# Main.net
KiCad netlist of a schematic drawn in Altium Designer
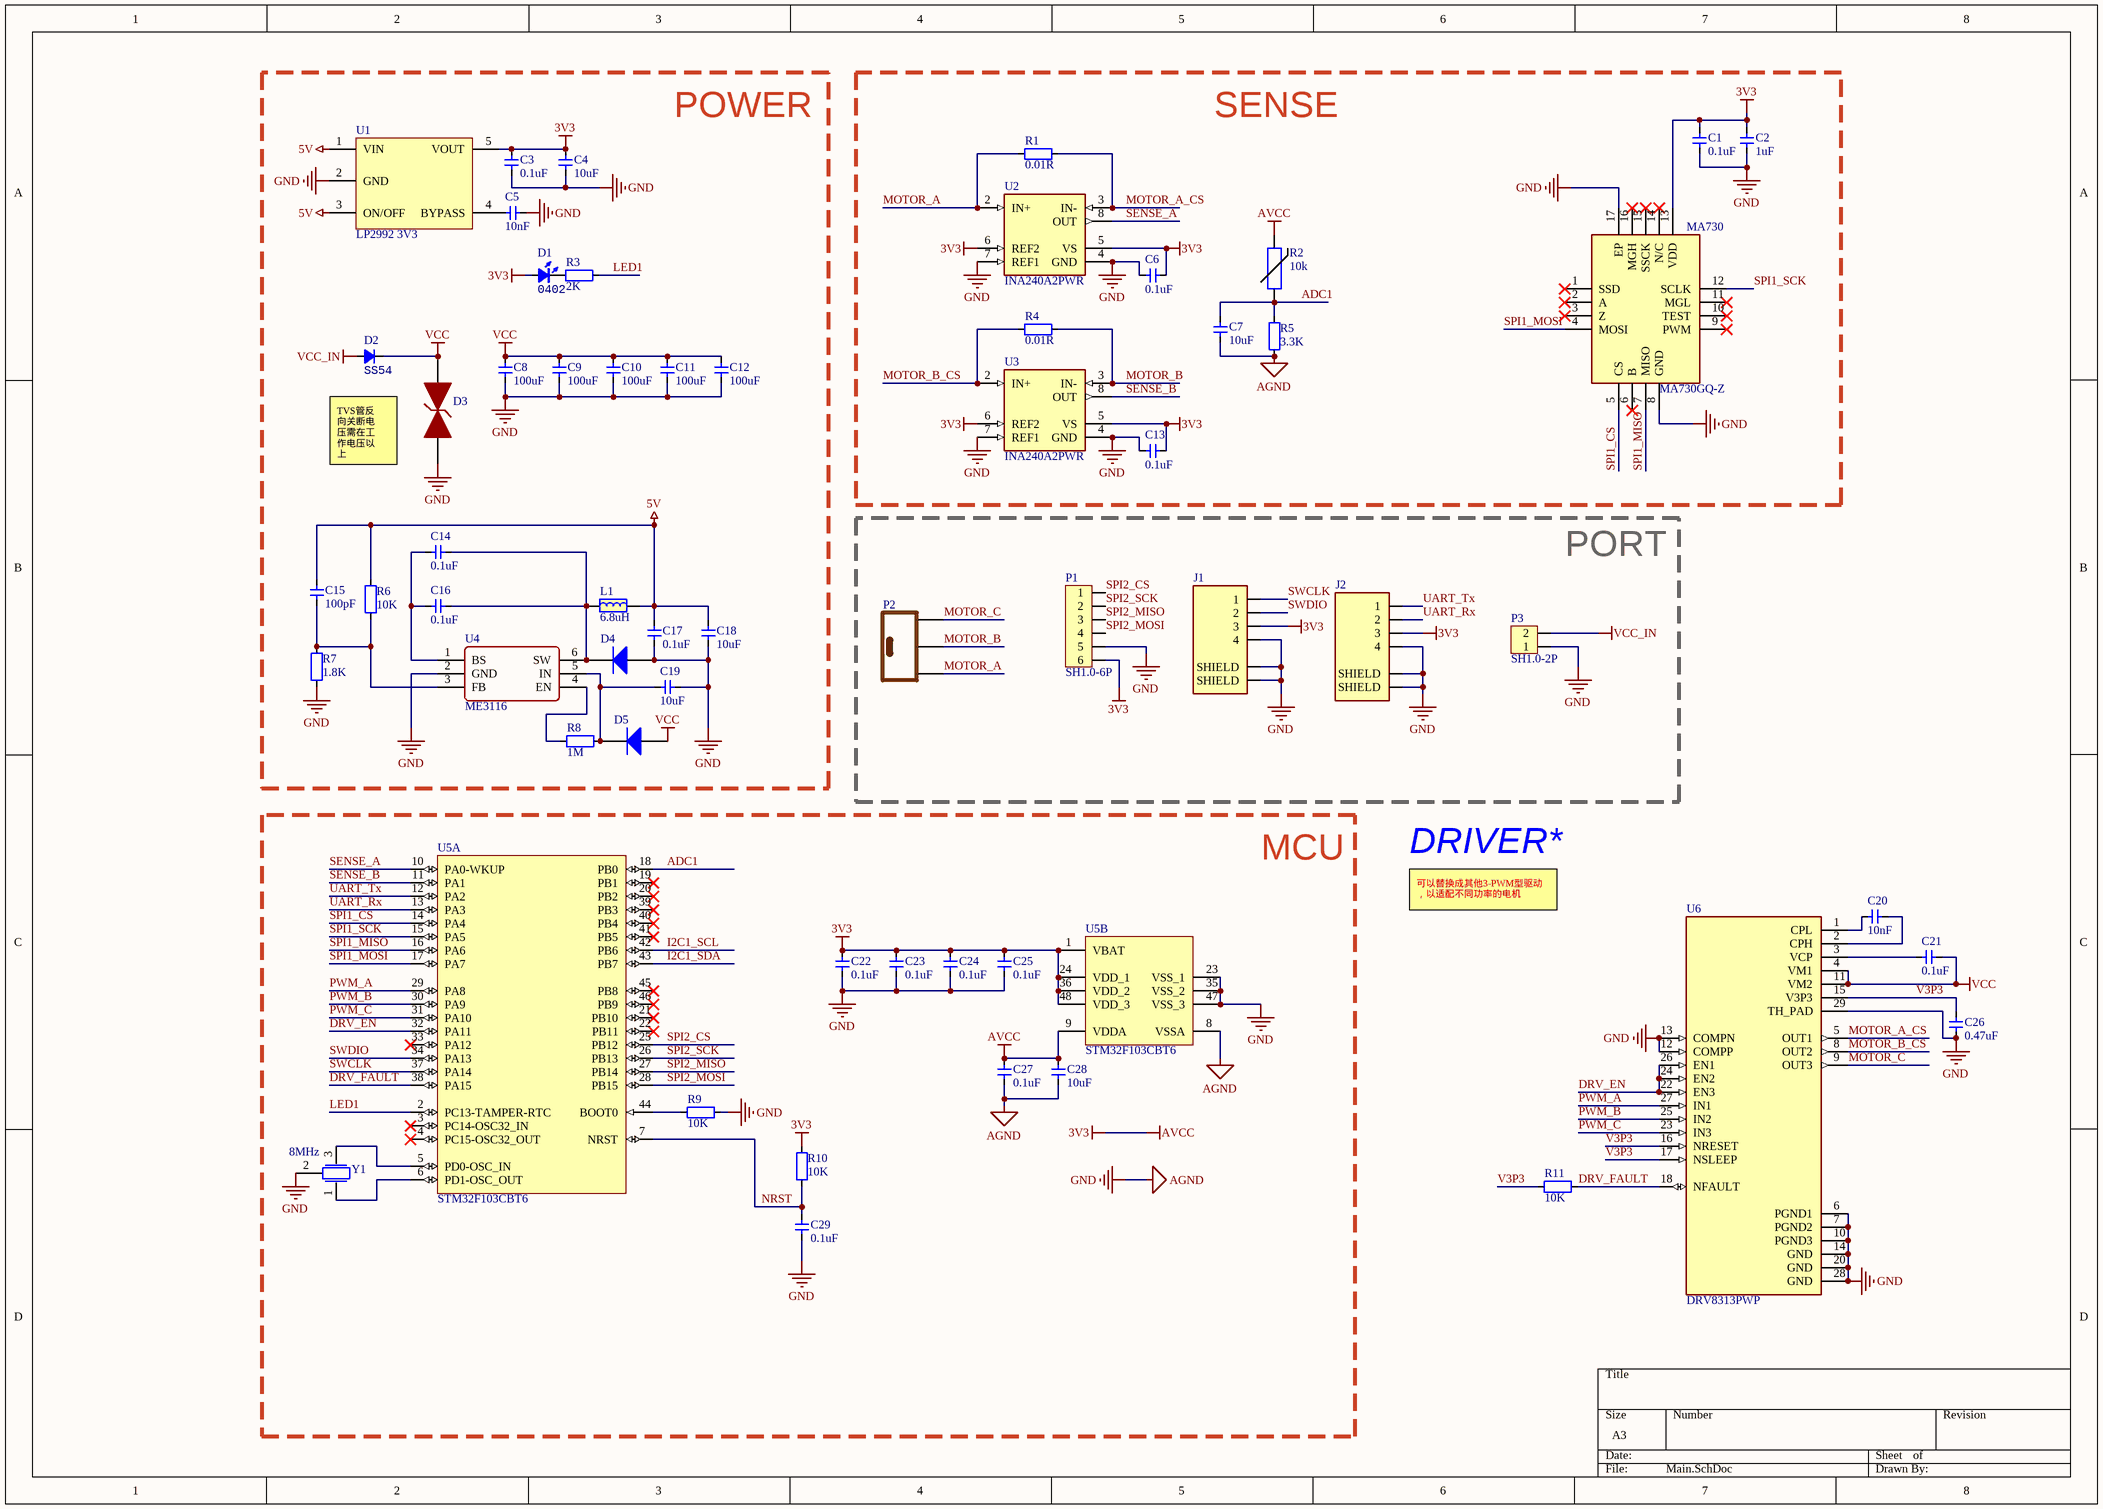
[diagram p0: Main.SchDoc]

(export (version "E")
  (design (tool "Eeschema 10.0.6"))
  (components
    (comp (ref "C1")
      (value "0.1uF")
      (footprint "CAP_0402")
      (description "Capacitor")
      (libsource (lib "Ctrl-FOC-Lite") (part "电容-0402"))
    )
    (comp (ref "C2")
      (value "1uF")
      (footprint "CAP_0402")
      (description "Capacitor")
      (libsource (lib "Ctrl-FOC-Lite") (part "电容-0402"))
    )
    (comp (ref "C3")
      (value "0.1uF")
      (footprint "CAP_0402")
      (description "Capacitor")
      (libsource (lib "MyPcbLib") (part "电容-0402"))
    )
    (comp (ref "C4")
      (value "10uF")
      (footprint "CAP_0402")
      (description "Capacitor")
      (libsource (lib "MyPcbLib") (part "电容-0402"))
    )
    (comp (ref "C5")
      (value "10nF")
      (footprint "CAP_0402")
      (description "Capacitor")
      (libsource (lib "MyPcbLib") (part "电容-0402"))
    )
    (comp (ref "C6")
      (value "0.1uF")
      (footprint "CAP_0402")
      (description "Capacitor")
      (libsource (lib "MyPcbLib") (part "电容-0402"))
    )
    (comp (ref "C7")
      (value "10uF")
      (footprint "CAP_0402")
      (description "Capacitor")
      (libsource (lib "MyPcbLib") (part "电容-0402"))
    )
    (comp (ref "C8")
      (value "100uF")
      (footprint "1206-CAP")
      (description "Capacitor")
      (libsource (lib "MyPcbLib") (part "电容-1206"))
    )
    (comp (ref "C9")
      (value "100uF")
      (footprint "1206-CAP")
      (description "Capacitor")
      (libsource (lib "MyPcbLib") (part "电容-1206"))
    )
    (comp (ref "C10")
      (value "100uF")
      (footprint "1206-CAP")
      (description "Capacitor")
      (libsource (lib "MyPcbLib") (part "电容-1206"))
    )
    (comp (ref "C11")
      (value "100uF")
      (footprint "1206-CAP")
      (description "Capacitor")
      (libsource (lib "MyPcbLib") (part "电容-1206"))
    )
    (comp (ref "C12")
      (value "100uF")
      (footprint "1206-CAP")
      (description "Capacitor")
      (libsource (lib "MyPcbLib") (part "电容-1206"))
    )
    (comp (ref "C13")
      (value "0.1uF")
      (footprint "CAP_0402")
      (description "Capacitor")
      (libsource (lib "MyPcbLib") (part "电容-0402"))
    )
    (comp (ref "C14")
      (value "0.1uF")
      (footprint "CAP_0402")
      (description "Capacitor")
      (libsource (lib "MyPcbLib") (part "电容-0402"))
    )
    (comp (ref "C15")
      (value "100pF")
      (footprint "CAP_0402")
      (description "Capacitor")
      (libsource (lib "MyPcbLib") (part "电容-0402"))
    )
    (comp (ref "C16")
      (value "0.1uF")
      (footprint "CAP_0402")
      (description "Capacitor")
      (libsource (lib "MyPcbLib") (part "电容-0402"))
    )
    (comp (ref "C17")
      (value "0.1uF")
      (footprint "CAP_0402")
      (description "Capacitor")
      (libsource (lib "MyPcbLib") (part "电容-0402"))
    )
    (comp (ref "C18")
      (value "10uF")
      (footprint "CAP_0402")
      (description "Capacitor")
      (libsource (lib "MyPcbLib") (part "电容-0402"))
    )
    (comp (ref "C19")
      (value "10uF")
      (footprint "CAP_0402")
      (description "Capacitor")
      (libsource (lib "MyPcbLib") (part "电容-0402"))
    )
    (comp (ref "C20")
      (value "10nF")
      (footprint "CAP_0402")
      (description "Capacitor")
      (libsource (lib "MyPcbLib") (part "电容-0402"))
    )
    (comp (ref "C21")
      (value "0.1uF")
      (footprint "CAP_0402")
      (description "Capacitor")
      (libsource (lib "MyPcbLib") (part "电容-0402"))
    )
    (comp (ref "C22")
      (value "0.1uF")
      (footprint "CAP_0402")
      (description "Capacitor")
      (libsource (lib "MyPcbLib") (part "电容-0402"))
    )
    (comp (ref "C23")
      (value "0.1uF")
      (footprint "CAP_0402")
      (description "Capacitor")
      (libsource (lib "MyPcbLib") (part "电容-0402"))
    )
    (comp (ref "C24")
      (value "0.1uF")
      (footprint "CAP_0402")
      (description "Capacitor")
      (libsource (lib "MyPcbLib") (part "电容-0402"))
    )
    (comp (ref "C25")
      (value "0.1uF")
      (footprint "CAP_0402")
      (description "Capacitor")
      (libsource (lib "MyPcbLib") (part "电容-0402"))
    )
    (comp (ref "C26")
      (value "0.47uF")
      (footprint "CAP_0402")
      (description "Capacitor")
      (libsource (lib "MyPcbLib") (part "电容-0402"))
    )
    (comp (ref "C27")
      (value "0.1uF")
      (footprint "CAP_0402")
      (description "Capacitor")
      (libsource (lib "MyPcbLib") (part "电容-0402"))
    )
    (comp (ref "C28")
      (value "10uF")
      (footprint "CAP_0402")
      (description "Capacitor")
      (libsource (lib "MyPcbLib") (part "电容-0402"))
    )
    (comp (ref "C29")
      (value "0.1uF")
      (footprint "CAP_0402")
      (description "Capacitor")
      (libsource (lib "MyPcbLib") (part "电容-0402"))
    )
    (comp (ref "D1")
      (value "color?")
      (footprint "LED_0402_RED")
      (description "LED")
      (fields (field (name "TYPE") "0402"))
      (libsource (lib "KitSprout") (part "LED_0402"))
    )
    (comp (ref "D2")
      (value "SS54")
      (footprint "DO-214AC")
      (description "Diode")
      (libsource (lib "KitSprout") (part "Diode_SMA"))
    )
    (comp (ref "D3")
      (value "SMBJ28CA")
      (footprint "SMBJ-CA_MFG")
      (libsource (lib "MyPcbLib") (part "SMBJ28CA"))
    )
    (comp (ref "D4")
      (value "二极管-5B5819WS")
      (footprint "SOD-323")
      (description "40V")
      (libsource (lib "MyPcbLib") (part "二极管-5B5817WS"))
    )
    (comp (ref "D5")
      (value "二极管-5B5819WS")
      (footprint "SOD-323")
      (description "40V")
      (libsource (lib "MyPcbLib") (part "二极管-5B5817WS"))
    )
    (comp (ref "J1")
      (value "SM04B-SRSS-TB(LF)(SN)")
      (footprint "JST_SM04B-SRSS-TB(LF)(SN)")
      (description "Connector Header Surface Mount, Right Angle 4 position 0.039 _1.00mm_")
      (fields (field (name "MF") "JST Sales") (field (name "MP") "SM04B-SRSS-TB_LF__SN_"))
      (libsource (lib "Ctrl-FOC-Lite") (part "SM04B-SRSS-TB(LF)(SN)"))
    )
    (comp (ref "J2")
      (value "SM04B-SRSS-TB(LF)(SN)")
      (footprint "JST_SM04B-SRSS-TB(LF)(SN)")
      (description "Connector Header Surface Mount, Right Angle 4 position 0.039 _1.00mm_")
      (fields (field (name "MF") "JST Sales") (field (name "MP") "SM04B-SRSS-TB_LF__SN_"))
      (libsource (lib "Ctrl-FOC-Lite") (part "SM04B-SRSS-TB(LF)(SN)"))
    )
    (comp (ref "L1") (value "6.8uH") (footprint "IND-201612") (libsource (lib "MyPcbLib") (part "电感-201612")))
    (comp (ref "MA730")
      (value "MA730GQ-Z")
      (footprint "SamacSys:QFN50P300X300X100-17N-D")
      (description "Integrated Circuit")
      (fields (field (name "MOUSER PART NUMBER") "946-MA730GQ-Z"))
      (libsource (lib "*") (part "MA730GQ-Z"))
    )
    (comp (ref "P1")
      (value "SH1.0-6P")
      (footprint "SH1.0-6P")
      (libsource (lib "Ctrl-FOC-Lite") (part "SH1.0-6P"))
    )
    (comp (ref "P2")
      (value "电机接插件-3P")
      (footprint "AMASS-MR30-M")
      (description "AMASS MR30")
      (libsource (lib "MyPcbLib") (part "电机接插件-3P"))
    )
    (comp (ref "P3")
      (value "SH1.0-2P")
      (footprint "SH1.0-2P")
      (libsource (lib "Ctrl-FOC-Lite") (part "SH1.0-2P"))
    )
    (comp (ref "R1")
      (value "0.01R")
      (footprint "1206-RES")
      (description "Resistor")
      (libsource (lib "MyPcbLib") (part "电阻-1206"))
    )
    (comp (ref "R2")
      (value "10k")
      (footprint "RES_0402")
      (description "THERMISTOR 10K OHM NTC 0402 SMD")
      (fields (field (name "Comment") "NCP15XH103F03RC"))
      (libsource (lib "MyPcbLib") (part "NCP15XH103F03RC"))
    )
    (comp (ref "R3")
      (value "2K")
      (footprint "RES_0402")
      (description "Resistor")
      (libsource (lib "") (part "电阻-0402_1"))
    )
    (comp (ref "R4")
      (value "0.01R")
      (footprint "1206-RES")
      (description "Resistor")
      (libsource (lib "MyPcbLib") (part "电阻-1206"))
    )
    (comp (ref "R5")
      (value "3.3K")
      (footprint "RES_0402")
      (description "Resistor")
      (libsource (lib "MyPcbLib") (part "电阻-0402"))
    )
    (comp (ref "R6")
      (value "10K")
      (footprint "RES_0402")
      (description "Resistor")
      (libsource (lib "MyPcbLib") (part "电阻-0402"))
    )
    (comp (ref "R7")
      (value "1.8K")
      (footprint "RES_0402")
      (description "Resistor")
      (libsource (lib "MyPcbLib") (part "电阻-0402"))
    )
    (comp (ref "R8")
      (value "1M")
      (footprint "RES_0402")
      (description "Resistor")
      (libsource (lib "") (part "电阻-0402_1"))
    )
    (comp (ref "R9")
      (value "10K")
      (footprint "RES_0402")
      (description "Resistor")
      (libsource (lib "") (part "电阻-0402_1"))
    )
    (comp (ref "R10")
      (value "10K")
      (footprint "RES_0402")
      (description "Resistor")
      (libsource (lib "MyPcbLib") (part "电阻-0402"))
    )
    (comp (ref "R11")
      (value "10K")
      (footprint "RES_0402")
      (description "Resistor")
      (libsource (lib "") (part "电阻-0402_2"))
    )
    (comp (ref "U1")
      (value "LP2992 3V3")
      (footprint "SOT23-5")
      (description "LDO")
      (libsource (lib "MyPcbLib") (part "LP2992"))
    )
    (comp (ref "U2")
      (value "INA240A2PWR")
      (footprint "SOP65 P640X120-8N")
      (fields (field (name "MF") "Texas Instruments"))
      (libsource (lib "mLib") (part "INA240A2PWR"))
    )
    (comp (ref "U3")
      (value "INA240A2PWR")
      (footprint "SOP65 P640X120-8N")
      (fields (field (name "MF") "Texas Instruments"))
      (libsource (lib "mLib") (part "INA240A2PWR"))
    )
    (comp (ref "U4")
      (value "ME3116")
      (footprint "SOT23-6")
      (description "DC-DC")
      (libsource (lib "MyPcbLib") (part "ME3116"))
    )
    (comp (ref "U5")
      (value "STM32F103CBT6")
      (footprint "LQFP-48")
      (libsource (lib "STMicroelectronics STM32 F1") (part "STM32F103CBT6"))
    )
    (comp (ref "U6")
      (value "DRV8313PWP")
      (footprint "HTSSOP-28")
      (description "65-V max, 3-A peak 3-phase motor driver 28-HTSSOP -40 to 125")
      (fields (field (name "MF") "Texas Instruments"))
      (libsource (lib "MyPcbLib") (part "DRV8313PWP"))
    )
    (comp (ref "Y1")
      (value "8MHz")
      (footprint "晶振-3P")
      (description "村田贴片")
      (libsource (lib "MyPcbLib") (part "晶振-3Pin"))
    )
  )
  (nets
    (net (code "1") (name "/ADC1") (class "Default")
      (node (ref "C7") (pin "2") (pinfunction "2_2") (pintype "passive"))
      (node (ref "R2") (pin "1") (pinfunction "0_1") (pintype "passive"))
      (node (ref "R5") (pin "2") (pinfunction "2_2") (pintype "passive"))
      (node (ref "U5") (pin "18") (pinfunction "PB0_18") (pintype "bidirectional"))
    )
    (net (code "2") (name "/DRV_EN") (class "Default")
      (node (ref "U5") (pin "32") (pinfunction "PA11_32") (pintype "bidirectional"))
      (node (ref "U6") (pin "22") (pinfunction "EN3_22") (pintype "input"))
      (node (ref "U6") (pin "24") (pinfunction "EN2_24") (pintype "input"))
      (node (ref "U6") (pin "26") (pinfunction "EN1_26") (pintype "input"))
    )
    (net (code "3") (name "/DRV_FAULT") (class "Default")
      (node (ref "R11") (pin "2") (pinfunction "2_2") (pintype "passive"))
      (node (ref "U5") (pin "38") (pinfunction "PA15_38") (pintype "bidirectional"))
      (node (ref "U6") (pin "18") (pinfunction "NFAULT_18") (pintype "bidirectional"))
    )
    (net (code "4") (name "/I2C1_SCL") (class "Default")
      (node (ref "U5") (pin "42") (pinfunction "PB6_42") (pintype "bidirectional"))
    )
    (net (code "5") (name "/I2C1_SDA") (class "Default")
      (node (ref "U5") (pin "43") (pinfunction "PB7_43") (pintype "bidirectional"))
    )
    (net (code "6") (name "/LED1") (class "Default")
      (node (ref "R3") (pin "1") (pinfunction "1_1") (pintype "passive"))
      (node (ref "U5") (pin "2") (pinfunction "PC13-TAMPER-RTC_2") (pintype "bidirectional"))
    )
    (net (code "7") (name "/MOTOR_A") (class "Default")
      (node (ref "P2") (pin "1") (pinfunction "1_1") (pintype "passive"))
      (node (ref "R1") (pin "1") (pinfunction "1_1") (pintype "passive"))
      (node (ref "U2") (pin "2") (pinfunction "IN+_2") (pintype "input"))
    )
    (net (code "8") (name "/MOTOR_A_CS") (class "Default")
      (node (ref "R1") (pin "2") (pinfunction "2_2") (pintype "passive"))
      (node (ref "U2") (pin "3") (pinfunction "IN-_3") (pintype "input"))
      (node (ref "U6") (pin "5") (pinfunction "OUT1_5") (pintype "output"))
    )
    (net (code "9") (name "/MOTOR_B") (class "Default")
      (node (ref "P2") (pin "2") (pinfunction "2_2") (pintype "passive"))
      (node (ref "R4") (pin "2") (pinfunction "2_2") (pintype "passive"))
      (node (ref "U3") (pin "3") (pinfunction "IN-_3") (pintype "input"))
    )
    (net (code "10") (name "/MOTOR_B_CS") (class "Default")
      (node (ref "R4") (pin "1") (pinfunction "1_1") (pintype "passive"))
      (node (ref "U3") (pin "2") (pinfunction "IN+_2") (pintype "input"))
      (node (ref "U6") (pin "8") (pinfunction "OUT2_8") (pintype "output"))
    )
    (net (code "11") (name "/MOTOR_C") (class "Default")
      (node (ref "P2") (pin "3") (pinfunction "3_3") (pintype "passive"))
      (node (ref "U6") (pin "9") (pinfunction "OUT3_9") (pintype "output"))
    )
    (net (code "12") (name "/NRST") (class "Default")
      (node (ref "C29") (pin "2") (pinfunction "2_2") (pintype "passive"))
      (node (ref "R10") (pin "1") (pinfunction "1_1") (pintype "passive"))
      (node (ref "U5") (pin "7") (pinfunction "NRST_7") (pintype "bidirectional"))
    )
    (net (code "13") (name "/PWM_A") (class "Default")
      (node (ref "U5") (pin "29") (pinfunction "PA8_29") (pintype "bidirectional"))
      (node (ref "U6") (pin "27") (pinfunction "IN1_27") (pintype "input"))
    )
    (net (code "14") (name "/PWM_B") (class "Default")
      (node (ref "U5") (pin "30") (pinfunction "PA9_30") (pintype "bidirectional"))
      (node (ref "U6") (pin "25") (pinfunction "IN2_25") (pintype "input"))
    )
    (net (code "15") (name "/PWM_C") (class "Default")
      (node (ref "U5") (pin "31") (pinfunction "PA10_31") (pintype "bidirectional"))
      (node (ref "U6") (pin "23") (pinfunction "IN3_23") (pintype "input"))
    )
    (net (code "16") (name "/SENSE_A") (class "Default")
      (node (ref "U2") (pin "8") (pinfunction "OUT_8") (pintype "output"))
      (node (ref "U5") (pin "10") (pinfunction "PA0-WKUP_10") (pintype "bidirectional"))
    )
    (net (code "17") (name "/SENSE_B") (class "Default")
      (node (ref "U3") (pin "8") (pinfunction "OUT_8") (pintype "output"))
      (node (ref "U5") (pin "11") (pinfunction "PA1_11") (pintype "bidirectional"))
    )
    (net (code "18") (name "/SPI1_CS") (class "Default")
      (node (ref "MA730") (pin "5") (pinfunction "CS_5") (pintype "passive"))
      (node (ref "U5") (pin "14") (pinfunction "PA4_14") (pintype "bidirectional"))
    )
    (net (code "19") (name "/SPI1_MISO") (class "Default")
      (node (ref "MA730") (pin "7") (pinfunction "MISO_7") (pintype "passive"))
      (node (ref "U5") (pin "16") (pinfunction "PA6_16") (pintype "bidirectional"))
    )
    (net (code "20") (name "/SPI1_MOSI") (class "Default")
      (node (ref "MA730") (pin "4") (pinfunction "MOSI_4") (pintype "passive"))
      (node (ref "U5") (pin "17") (pinfunction "PA7_17") (pintype "bidirectional"))
    )
    (net (code "21") (name "/SPI1_SCK") (class "Default")
      (node (ref "MA730") (pin "12") (pinfunction "SCLK_12") (pintype "passive"))
      (node (ref "U5") (pin "15") (pinfunction "PA5_15") (pintype "bidirectional"))
    )
    (net (code "22") (name "/SPI2_CS") (class "Default")
      (node (ref "P1") (pin "1") (pinfunction "1_1") (pintype "passive"))
      (node (ref "U5") (pin "25") (pinfunction "PB12_25") (pintype "bidirectional"))
    )
    (net (code "23") (name "/SPI2_MISO") (class "Default")
      (node (ref "P1") (pin "3") (pinfunction "3_3") (pintype "passive"))
      (node (ref "U5") (pin "27") (pinfunction "PB14_27") (pintype "bidirectional"))
    )
    (net (code "24") (name "/SPI2_MOSI") (class "Default")
      (node (ref "P1") (pin "4") (pinfunction "4_4") (pintype "passive"))
      (node (ref "U5") (pin "28") (pinfunction "PB15_28") (pintype "bidirectional"))
    )
    (net (code "25") (name "/SPI2_SCK") (class "Default")
      (node (ref "P1") (pin "2") (pinfunction "2_2") (pintype "passive"))
      (node (ref "U5") (pin "26") (pinfunction "PB13_26") (pintype "bidirectional"))
    )
    (net (code "26") (name "/SWCLK") (class "Default")
      (node (ref "J1") (pin "1") (pinfunction "1_1") (pintype "passive"))
      (node (ref "U5") (pin "37") (pinfunction "PA14_37") (pintype "bidirectional"))
    )
    (net (code "27") (name "/SWDIO") (class "Default")
      (node (ref "J1") (pin "2") (pinfunction "2_2") (pintype "passive"))
      (node (ref "U5") (pin "34") (pinfunction "PA13_34") (pintype "bidirectional"))
    )
    (net (code "28") (name "/UART_Rx") (class "Default")
      (node (ref "J2") (pin "2") (pinfunction "2_2") (pintype "passive"))
      (node (ref "U5") (pin "13") (pinfunction "PA3_13") (pintype "bidirectional"))
    )
    (net (code "29") (name "/UART_Tx") (class "Default")
      (node (ref "J2") (pin "1") (pinfunction "1_1") (pintype "passive"))
      (node (ref "U5") (pin "12") (pinfunction "PA2_12") (pintype "bidirectional"))
    )
    (net (code "30") (name "/V3P3") (class "Default")
      (node (ref "C26") (pin "2") (pinfunction "2_2") (pintype "passive"))
      (node (ref "R11") (pin "1") (pinfunction "1_1") (pintype "passive"))
      (node (ref "U6") (pin "15") (pinfunction "V3P3_15") (pintype "power_in"))
      (node (ref "U6") (pin "16") (pinfunction "NRESET_16") (pintype "input"))
      (node (ref "U6") (pin "17") (pinfunction "NSLEEP_17") (pintype "input"))
    )
    (net (code "31") (name "3V3") (class "Default")
      (node (ref "C1") (pin "1") (pinfunction "1_1") (pintype "passive"))
      (node (ref "C13") (pin "1") (pinfunction "1_1") (pintype "passive"))
      (node (ref "C2") (pin "1") (pinfunction "1_1") (pintype "passive"))
      (node (ref "C22") (pin "2") (pinfunction "2_2") (pintype "passive"))
      (node (ref "C23") (pin "2") (pinfunction "2_2") (pintype "passive"))
      (node (ref "C24") (pin "2") (pinfunction "2_2") (pintype "passive"))
      (node (ref "C25") (pin "2") (pinfunction "2_2") (pintype "passive"))
      (node (ref "C27") (pin "2") (pinfunction "2_2") (pintype "passive"))
      (node (ref "C28") (pin "2") (pinfunction "2_2") (pintype "passive"))
      (node (ref "C3") (pin "2") (pinfunction "2_2") (pintype "passive"))
      (node (ref "C4") (pin "2") (pinfunction "2_2") (pintype "passive"))
      (node (ref "C6") (pin "1") (pinfunction "1_1") (pintype "passive"))
      (node (ref "D1") (pin "1") (pinfunction "A_1") (pintype "passive"))
      (node (ref "J1") (pin "3") (pinfunction "3_3") (pintype "passive"))
      (node (ref "J2") (pin "3") (pinfunction "3_3") (pintype "passive"))
      (node (ref "MA730") (pin "13") (pinfunction "VDD_13") (pintype "passive"))
      (node (ref "P1") (pin "6") (pinfunction "6_6") (pintype "passive"))
      (node (ref "R10") (pin "2") (pinfunction "2_2") (pintype "passive"))
      (node (ref "R2") (pin "2") (pinfunction "0_2") (pintype "passive"))
      (node (ref "U1") (pin "5") (pinfunction "VOUT_5") (pintype "passive"))
      (node (ref "U2") (pin "5") (pinfunction "VS_5") (pintype "power_in"))
      (node (ref "U2") (pin "6") (pinfunction "REF2_6") (pintype "input"))
      (node (ref "U3") (pin "5") (pinfunction "VS_5") (pintype "power_in"))
      (node (ref "U3") (pin "6") (pinfunction "REF2_6") (pintype "input"))
      (node (ref "U5") (pin "1") (pinfunction "VBAT_1") (pintype "power_in"))
      (node (ref "U5") (pin "24") (pinfunction "VDD_1_24") (pintype "power_in"))
      (node (ref "U5") (pin "36") (pinfunction "VDD_2_36") (pintype "power_in"))
      (node (ref "U5") (pin "48") (pinfunction "VDD_3_48") (pintype "power_in"))
      (node (ref "U5") (pin "9") (pinfunction "VDDA_9") (pintype "power_in"))
    )
    (net (code "32") (name "5V") (class "Default")
      (node (ref "C15") (pin "1") (pinfunction "1_1") (pintype "passive"))
      (node (ref "C17") (pin "2") (pinfunction "2_2") (pintype "passive"))
      (node (ref "C18") (pin "2") (pinfunction "2_2") (pintype "passive"))
      (node (ref "L1") (pin "2") (pinfunction "2_2") (pintype "passive"))
      (node (ref "R6") (pin "2") (pinfunction "2_2") (pintype "passive"))
      (node (ref "U1") (pin "1") (pinfunction "VIN_1") (pintype "passive"))
      (node (ref "U1") (pin "3") (pinfunction "ON/OFF_3") (pintype "passive"))
    )
    (net (code "33") (name "AGND") (class "Default")
      (node (ref "C1") (pin "2") (pinfunction "2_2") (pintype "passive"))
      (node (ref "C10") (pin "1") (pinfunction "1_1") (pintype "passive"))
      (node (ref "C11") (pin "1") (pinfunction "1_1") (pintype "passive"))
      (node (ref "C12") (pin "1") (pinfunction "1_1") (pintype "passive"))
      (node (ref "C13") (pin "2") (pinfunction "2_2") (pintype "passive"))
      (node (ref "C17") (pin "1") (pinfunction "1_1") (pintype "passive"))
      (node (ref "C18") (pin "1") (pinfunction "1_1") (pintype "passive"))
      (node (ref "C19") (pin "1") (pinfunction "1_1") (pintype "passive"))
      (node (ref "C2") (pin "2") (pinfunction "2_2") (pintype "passive"))
      (node (ref "C22") (pin "1") (pinfunction "1_1") (pintype "passive"))
      (node (ref "C23") (pin "1") (pinfunction "1_1") (pintype "passive"))
      (node (ref "C24") (pin "1") (pinfunction "1_1") (pintype "passive"))
      (node (ref "C25") (pin "1") (pinfunction "1_1") (pintype "passive"))
      (node (ref "C26") (pin "1") (pinfunction "1_1") (pintype "passive"))
      (node (ref "C27") (pin "1") (pinfunction "1_1") (pintype "passive"))
      (node (ref "C28") (pin "1") (pinfunction "1_1") (pintype "passive"))
      (node (ref "C29") (pin "1") (pinfunction "1_1") (pintype "passive"))
      (node (ref "C3") (pin "1") (pinfunction "1_1") (pintype "passive"))
      (node (ref "C4") (pin "1") (pinfunction "1_1") (pintype "passive"))
      (node (ref "C5") (pin "1") (pinfunction "1_1") (pintype "passive"))
      (node (ref "C6") (pin "2") (pinfunction "2_2") (pintype "passive"))
      (node (ref "C7") (pin "1") (pinfunction "1_1") (pintype "passive"))
      (node (ref "C8") (pin "1") (pinfunction "1_1") (pintype "passive"))
      (node (ref "C9") (pin "1") (pinfunction "1_1") (pintype "passive"))
      (node (ref "D3") (pin "1") (pinfunction "1_1") (pintype "passive"))
      (node (ref "D4") (pin "1") (pinfunction "A_1") (pintype "passive"))
      (node (ref "J1") (pin "4") (pinfunction "4_4") (pintype "passive"))
      (node (ref "J1") (pin "S1") (pinfunction "SHIELD_S1") (pintype "passive"))
      (node (ref "J1") (pin "S2") (pinfunction "SHIELD_S2") (pintype "passive"))
      (node (ref "J2") (pin "4") (pinfunction "4_4") (pintype "passive"))
      (node (ref "J2") (pin "S1") (pinfunction "SHIELD_S1") (pintype "passive"))
      (node (ref "J2") (pin "S2") (pinfunction "SHIELD_S2") (pintype "passive"))
      (node (ref "MA730") (pin "17") (pinfunction "EP_17") (pintype "passive"))
      (node (ref "MA730") (pin "8") (pinfunction "GND_8") (pintype "passive"))
      (node (ref "P1") (pin "5") (pinfunction "5_5") (pintype "passive"))
      (node (ref "P3") (pin "1") (pinfunction "1_1") (pintype "passive"))
      (node (ref "R5") (pin "1") (pinfunction "1_1") (pintype "passive"))
      (node (ref "R7") (pin "1") (pinfunction "1_1") (pintype "passive"))
      (node (ref "R9") (pin "1") (pinfunction "1_1") (pintype "passive"))
      (node (ref "U1") (pin "2") (pinfunction "GND_2") (pintype "passive"))
      (node (ref "U2") (pin "4") (pinfunction "GND_4") (pintype "power_in"))
      (node (ref "U2") (pin "7") (pinfunction "REF1_7") (pintype "input"))
      (node (ref "U3") (pin "4") (pinfunction "GND_4") (pintype "power_in"))
      (node (ref "U3") (pin "7") (pinfunction "REF1_7") (pintype "input"))
      (node (ref "U4") (pin "2") (pinfunction "GND_2") (pintype "passive"))
      (node (ref "U5") (pin "23") (pinfunction "VSS_1_23") (pintype "power_in"))
      (node (ref "U5") (pin "35") (pinfunction "VSS_2_35") (pintype "power_in"))
      (node (ref "U5") (pin "47") (pinfunction "VSS_3_47") (pintype "power_in"))
      (node (ref "U5") (pin "8") (pinfunction "VSSA_8") (pintype "power_in"))
      (node (ref "U6") (pin "10") (pinfunction "PGND3_10") (pintype "power_in"))
      (node (ref "U6") (pin "12") (pinfunction "COMPP_12") (pintype "input"))
      (node (ref "U6") (pin "13") (pinfunction "COMPN_13") (pintype "input"))
      (node (ref "U6") (pin "14") (pinfunction "GND_14") (pintype "power_in"))
      (node (ref "U6") (pin "20") (pinfunction "GND_20") (pintype "power_in"))
      (node (ref "U6") (pin "28") (pinfunction "GND_28") (pintype "power_in"))
      (node (ref "U6") (pin "29") (pinfunction "TH_PAD_29") (pintype "power_in"))
      (node (ref "U6") (pin "6") (pinfunction "PGND1_6") (pintype "power_in"))
      (node (ref "U6") (pin "7") (pinfunction "PGND2_7") (pintype "power_in"))
      (node (ref "Y1") (pin "2") (pinfunction "2_2") (pintype "passive"))
    )
    (net (code "34") (name "Net-(D1-K)") (class "Default")
      (node (ref "D1") (pin "2") (pinfunction "K_2") (pintype "passive"))
      (node (ref "R3") (pin "2") (pinfunction "2_2") (pintype "passive"))
    )
    (net (code "35") (name "Net-(D4-K)") (class "Default")
      (node (ref "C14") (pin "1") (pinfunction "1_1") (pintype "passive"))
      (node (ref "C16") (pin "1") (pinfunction "1_1") (pintype "passive"))
      (node (ref "D4") (pin "2") (pinfunction "K_2") (pintype "passive"))
      (node (ref "L1") (pin "1") (pintype "passive"))
      (node (ref "U4") (pin "6") (pinfunction "SW_6") (pintype "passive"))
    )
    (net (code "36") (name "Net-(D5-K)") (class "Default")
      (node (ref "C19") (pin "2") (pinfunction "2_2") (pintype "passive"))
      (node (ref "D5") (pin "2") (pinfunction "K_2") (pintype "passive"))
      (node (ref "R8") (pin "1") (pinfunction "1_1") (pintype "passive"))
      (node (ref "U4") (pin "5") (pinfunction "IN_5") (pintype "passive"))
    )
    (net (code "37") (name "Net-(U1-BYPASS)") (class "Default")
      (node (ref "C5") (pin "2") (pinfunction "2_2") (pintype "passive"))
      (node (ref "U1") (pin "4") (pinfunction "BYPASS_4") (pintype "passive"))
    )
    (net (code "38") (name "Net-(U4-BS)") (class "Default")
      (node (ref "C14") (pin "2") (pinfunction "2_2") (pintype "passive"))
      (node (ref "C16") (pin "2") (pinfunction "2_2") (pintype "passive"))
      (node (ref "U4") (pin "1") (pinfunction "BS_1") (pintype "passive"))
    )
    (net (code "39") (name "Net-(U4-EN)") (class "Default")
      (node (ref "R8") (pin "2") (pinfunction "2_2") (pintype "passive"))
      (node (ref "U4") (pin "4") (pinfunction "EN_4") (pintype "passive"))
    )
    (net (code "40") (name "Net-(U4-FB)") (class "Default")
      (node (ref "C15") (pin "2") (pinfunction "2_2") (pintype "passive"))
      (node (ref "R6") (pin "1") (pinfunction "1_1") (pintype "passive"))
      (node (ref "R7") (pin "2") (pinfunction "2_2") (pintype "passive"))
      (node (ref "U4") (pin "3") (pinfunction "FB_3") (pintype "passive"))
    )
    (net (code "41") (name "Net-(U5A-BOOT0)") (class "Default")
      (node (ref "R9") (pin "2") (pinfunction "2_2") (pintype "passive"))
      (node (ref "U5") (pin "44") (pinfunction "BOOT0_44") (pintype "input"))
    )
    (net (code "42") (name "Net-(U5A-PD0-OSC_IN)") (class "Default")
      (node (ref "U5") (pin "5") (pinfunction "PD0-OSC_IN_5") (pintype "bidirectional"))
      (node (ref "Y1") (pin "3") (pinfunction "3_3") (pintype "passive"))
    )
    (net (code "43") (name "Net-(U5A-PD1-OSC_OUT)") (class "Default")
      (node (ref "U5") (pin "6") (pinfunction "PD1-OSC_OUT_6") (pintype "bidirectional"))
      (node (ref "Y1") (pin "1") (pinfunction "1_1") (pintype "passive"))
    )
    (net (code "44") (name "Net-(U6-CPH)") (class "Default")
      (node (ref "C20") (pin "2") (pinfunction "2_2") (pintype "passive"))
      (node (ref "U6") (pin "2") (pinfunction "CPH_2") (pintype "power_in"))
    )
    (net (code "45") (name "Net-(U6-CPL)") (class "Default")
      (node (ref "C20") (pin "1") (pinfunction "1_1") (pintype "passive"))
      (node (ref "U6") (pin "1") (pinfunction "CPL_1") (pintype "power_in"))
    )
    (net (code "46") (name "Net-(U6-VCP)") (class "Default")
      (node (ref "C21") (pin "1") (pinfunction "1_1") (pintype "passive"))
      (node (ref "U6") (pin "3") (pinfunction "VCP_3") (pintype "power_in"))
    )
    (net (code "47") (name "VCC") (class "Default")
      (node (ref "C10") (pin "2") (pinfunction "2_2") (pintype "passive"))
      (node (ref "C11") (pin "2") (pinfunction "2_2") (pintype "passive"))
      (node (ref "C12") (pin "2") (pinfunction "2_2") (pintype "passive"))
      (node (ref "C21") (pin "2") (pinfunction "2_2") (pintype "passive"))
      (node (ref "C8") (pin "2") (pinfunction "2_2") (pintype "passive"))
      (node (ref "C9") (pin "2") (pinfunction "2_2") (pintype "passive"))
      (node (ref "D2") (pin "2") (pinfunction "K_2") (pintype "passive"))
      (node (ref "D3") (pin "2") (pinfunction "2_2") (pintype "passive"))
      (node (ref "D5") (pin "1") (pinfunction "A_1") (pintype "passive"))
      (node (ref "U6") (pin "11") (pinfunction "VM2_11") (pintype "power_in"))
      (node (ref "U6") (pin "4") (pinfunction "VM1_4") (pintype "power_in"))
    )
    (net (code "48") (name "VCC_IN") (class "Default")
      (node (ref "D2") (pin "1") (pinfunction "A_1") (pintype "passive"))
      (node (ref "P3") (pin "2") (pinfunction "2_2") (pintype "passive"))
    )
    (net (code "49") (name "unconnected-(MA730-A-Pad2)") (class "Default")
      (node (ref "MA730") (pin "2") (pinfunction "A_2") (pintype "passive+no_connect"))
    )
    (net (code "50") (name "unconnected-(MA730-B-Pad6)") (class "Default")
      (node (ref "MA730") (pin "6") (pinfunction "B_6") (pintype "passive+no_connect"))
    )
    (net (code "51") (name "unconnected-(MA730-MGH-Pad16)") (class "Default")
      (node (ref "MA730") (pin "16") (pinfunction "MGH_16") (pintype "passive+no_connect"))
    )
    (net (code "52") (name "unconnected-(MA730-MGL-Pad11)") (class "Default")
      (node (ref "MA730") (pin "11") (pinfunction "MGL_11") (pintype "passive+no_connect"))
    )
    (net (code "53") (name "unconnected-(MA730-N{slash}C-Pad14)") (class "Default")
      (node (ref "MA730") (pin "14") (pinfunction "N/C_14") (pintype "passive+no_connect"))
    )
    (net (code "54") (name "unconnected-(MA730-PWM-Pad9)") (class "Default")
      (node (ref "MA730") (pin "9") (pinfunction "PWM_9") (pintype "passive+no_connect"))
    )
    (net (code "55") (name "unconnected-(MA730-SSCK-Pad15)") (class "Default")
      (node (ref "MA730") (pin "15") (pinfunction "SSCK_15") (pintype "passive+no_connect"))
    )
    (net (code "56") (name "unconnected-(MA730-SSD-Pad1)") (class "Default")
      (node (ref "MA730") (pin "1") (pinfunction "SSD_1") (pintype "passive+no_connect"))
    )
    (net (code "57") (name "unconnected-(MA730-TEST-Pad10)") (class "Default")
      (node (ref "MA730") (pin "10") (pinfunction "TEST_10") (pintype "passive+no_connect"))
    )
    (net (code "58") (name "unconnected-(MA730-Z-Pad3)") (class "Default")
      (node (ref "MA730") (pin "3") (pinfunction "Z_3") (pintype "passive+no_connect"))
    )
    (net (code "59") (name "unconnected-(U5A-PA12-Pad33)") (class "Default")
      (node (ref "U5") (pin "33") (pinfunction "PA12_33") (pintype "bidirectional+no_connect"))
    )
    (net (code "60") (name "unconnected-(U5A-PB1-Pad19)") (class "Default")
      (node (ref "U5") (pin "19") (pinfunction "PB1_19") (pintype "bidirectional+no_connect"))
    )
    (net (code "61") (name "unconnected-(U5A-PB2-Pad20)") (class "Default")
      (node (ref "U5") (pin "20") (pinfunction "PB2_20") (pintype "bidirectional+no_connect"))
    )
    (net (code "62") (name "unconnected-(U5A-PB3-Pad39)") (class "Default")
      (node (ref "U5") (pin "39") (pinfunction "PB3_39") (pintype "bidirectional+no_connect"))
    )
    (net (code "63") (name "unconnected-(U5A-PB4-Pad40)") (class "Default")
      (node (ref "U5") (pin "40") (pinfunction "PB4_40") (pintype "bidirectional+no_connect"))
    )
    (net (code "64") (name "unconnected-(U5A-PB5-Pad41)") (class "Default")
      (node (ref "U5") (pin "41") (pinfunction "PB5_41") (pintype "bidirectional+no_connect"))
    )
    (net (code "65") (name "unconnected-(U5A-PB8-Pad45)") (class "Default")
      (node (ref "U5") (pin "45") (pinfunction "PB8_45") (pintype "bidirectional+no_connect"))
    )
    (net (code "66") (name "unconnected-(U5A-PB9-Pad46)") (class "Default")
      (node (ref "U5") (pin "46") (pinfunction "PB9_46") (pintype "bidirectional+no_connect"))
    )
    (net (code "67") (name "unconnected-(U5A-PB10-Pad21)") (class "Default")
      (node (ref "U5") (pin "21") (pinfunction "PB10_21") (pintype "bidirectional+no_connect"))
    )
    (net (code "68") (name "unconnected-(U5A-PB11-Pad22)") (class "Default")
      (node (ref "U5") (pin "22") (pinfunction "PB11_22") (pintype "bidirectional+no_connect"))
    )
    (net (code "69") (name "unconnected-(U5A-PC14-OSC32_IN-Pad3)") (class "Default")
      (node (ref "U5") (pin "3") (pinfunction "PC14-OSC32_IN_3") (pintype "bidirectional+no_connect"))
    )
    (net (code "70") (name "unconnected-(U5A-PC15-OSC32_OUT-Pad4)") (class "Default")
      (node (ref "U5") (pin "4") (pinfunction "PC15-OSC32_OUT_4") (pintype "bidirectional+no_connect"))
    )
  )
)
